# DebouncedButtons.net
KiCad netlist of a schematic drawn in Altium Designer
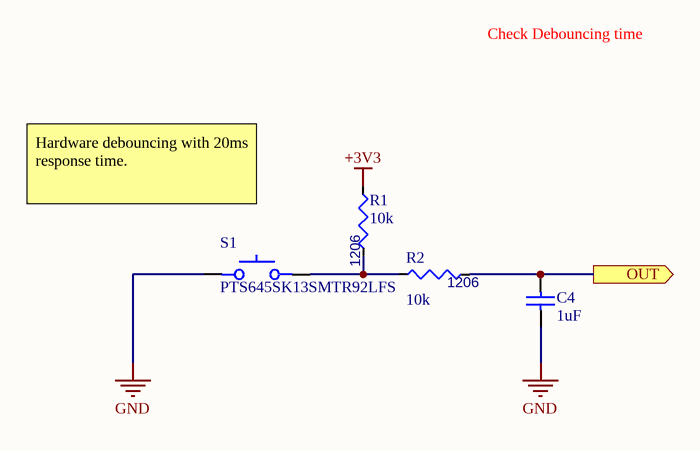
[diagram p0: DebouncedButtons.SchDoc]

(export (version "E")
  (design (tool "Eeschema 10.0.6"))
  (components
    (comp (ref "C4")
      (value "1uF")
      (footprint "C1206")
      (description "CER 1UF 50V X7R 1206")
      (fields (field (name "MADE BY") "Brennan Swanton") (field (name "REVIEWED BY") "Carter Allen"))
      (libsource (lib "USCRPL") (part "Symbol"))
    )
    (comp (ref "R1")
      (value "10k")
      (footprint "R1206")
      (description "10K OHM 1% 1/4W 1206")
      (fields (field (name "MADE BY") "Brennan Swanton") (field (name "REVIEWED BY") "Carter Allen"))
      (libsource (lib "") (part "Symbol_1"))
    )
    (comp (ref "R2")
      (value "10k")
      (footprint "R1206")
      (description "10K OHM 1% 1/4W 1206")
      (fields (field (name "MADE BY") "Brennan Swanton") (field (name "REVIEWED BY") "Carter Allen"))
      (libsource (lib "") (part "Symbol_1"))
    )
    (comp (ref "S1")
      (value "PTS645SK13SMTR92LFS")
      (footprint "PTS645SK13SMTR92LFS-Footprint-1")
      (description "SWITCH TACTILE SPST-NO 0.05A 12V")
      (fields (field (name "MANUFACTURER") "Digi-Key") (field (name "MADE BY") "Victor"))
      (libsource (lib "USCRPL") (part "PTS645SK13SMTR92LFS-Symbol-1"))
    )
  )
  (nets
    (net (code "1") (name "+3V3") (class "Default")
      (node (ref "R1") (pin "2") (pinfunction "2_2") (pintype "passive"))
    )
    (net (code "2") (name "/OUT") (class "Default")
      (node (ref "C4") (pin "2") (pinfunction "2_2") (pintype "passive"))
      (node (ref "R2") (pin "1") (pinfunction "1_1") (pintype "passive"))
    )
    (net (code "3") (name "GND") (class "Default")
      (node (ref "C4") (pin "1") (pinfunction "1_1") (pintype "passive"))
      (node (ref "S1") (pin "2") (pinfunction "2_2") (pintype "passive"))
    )
    (net (code "4") (name "Net-(R1-Pad1)") (class "Default")
      (node (ref "R1") (pin "1") (pinfunction "1_1") (pintype "passive"))
      (node (ref "R2") (pin "2") (pinfunction "2_2") (pintype "passive"))
      (node (ref "S1") (pin "1") (pinfunction "1_1") (pintype "passive"))
    )
  )
)
